# Pinout_Toygether_Sch.net
KiCad netlist of a schematic drawn in Altium Designer
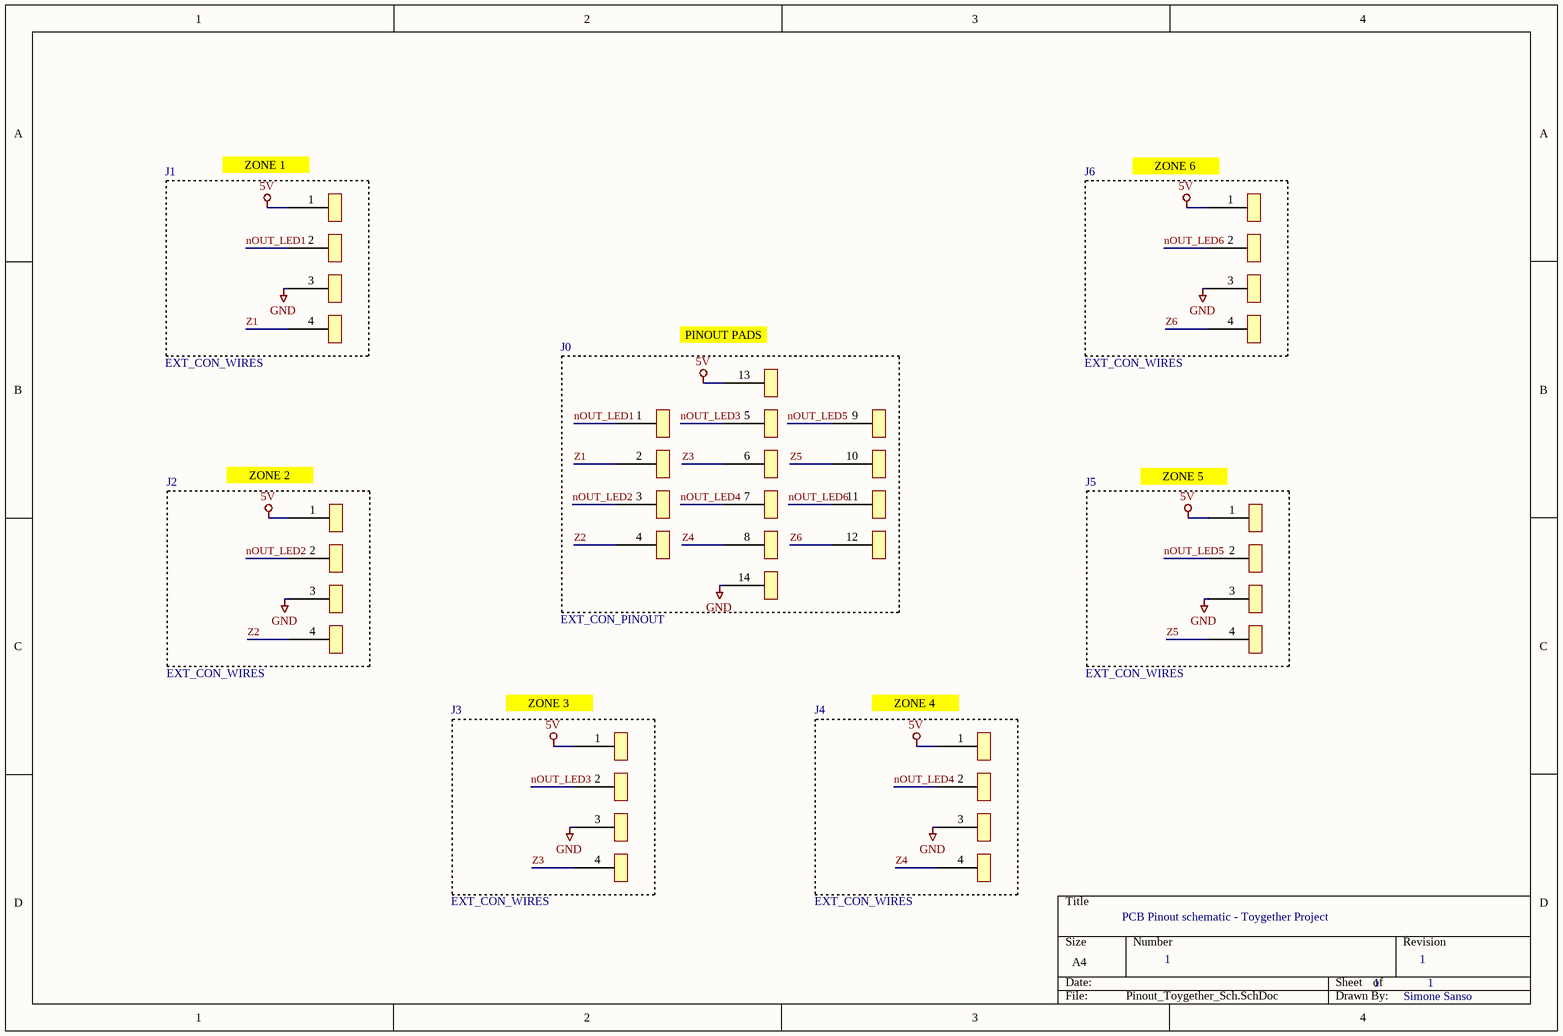
[diagram p0: Pinout_Toygether_Sch.SchDoc]

(export (version "E")
  (design (tool "Eeschema 10.0.6"))
  (components
    (comp (ref "J0")
      (value "EXT_CON_PINOUT")
      (footprint "EXT_CON_PINOUT_14P")
      (description "Pinout for the LEDs and capacitive touch sensors (on the plush toy)")
      (libsource (lib "Toygether_Schlib") (part "EXT_CON_PINOUT"))
    )
    (comp (ref "J1")
      (value "EXT_CON_WIRES")
      (footprint "EXT_CON_WIRES_4P")
      (description "Pads between pinout board and wires of the plush toy")
      (libsource (lib "Toygether_Schlib") (part "EXT_CON_WIRES"))
    )
    (comp (ref "J2")
      (value "EXT_CON_WIRES")
      (footprint "EXT_CON_WIRES_4P")
      (description "Pads between pinout board and wires of the plush toy")
      (libsource (lib "Toygether_Schlib") (part "EXT_CON_WIRES"))
    )
    (comp (ref "J3")
      (value "EXT_CON_WIRES")
      (footprint "EXT_CON_WIRES_4P")
      (description "Pads between pinout board and wires of the plush toy")
      (libsource (lib "Toygether_Schlib") (part "EXT_CON_WIRES"))
    )
    (comp (ref "J4")
      (value "EXT_CON_WIRES")
      (footprint "EXT_CON_WIRES_4P")
      (description "Pads between pinout board and wires of the plush toy")
      (libsource (lib "Toygether_Schlib") (part "EXT_CON_WIRES"))
    )
    (comp (ref "J5")
      (value "EXT_CON_WIRES")
      (footprint "EXT_CON_WIRES_4P")
      (description "Pads between pinout board and wires of the plush toy")
      (libsource (lib "Toygether_Schlib") (part "EXT_CON_WIRES"))
    )
    (comp (ref "J6")
      (value "EXT_CON_WIRES")
      (footprint "EXT_CON_WIRES_4P")
      (description "Pads between pinout board and wires of the plush toy")
      (libsource (lib "Toygether_Schlib") (part "EXT_CON_WIRES"))
    )
  )
  (nets
    (net (code "1") (name "/Z1") (class "Default")
      (node (ref "J0") (pin "2") (pintype "passive"))
      (node (ref "J1") (pin "4") (pintype "passive"))
    )
    (net (code "2") (name "/Z2") (class "Default")
      (node (ref "J0") (pin "4") (pintype "passive"))
      (node (ref "J2") (pin "4") (pintype "passive"))
    )
    (net (code "3") (name "/Z3") (class "Default")
      (node (ref "J0") (pin "6") (pintype "passive"))
      (node (ref "J3") (pin "4") (pintype "passive"))
    )
    (net (code "4") (name "/Z4") (class "Default")
      (node (ref "J0") (pin "8") (pintype "passive"))
      (node (ref "J4") (pin "4") (pintype "passive"))
    )
    (net (code "5") (name "/Z5") (class "Default")
      (node (ref "J0") (pin "10") (pintype "passive"))
      (node (ref "J5") (pin "4") (pintype "passive"))
    )
    (net (code "6") (name "/Z6") (class "Default")
      (node (ref "J0") (pin "12") (pintype "passive"))
      (node (ref "J6") (pin "4") (pintype "passive"))
    )
    (net (code "7") (name "/nOUT_LED1") (class "Default")
      (node (ref "J0") (pin "1") (pintype "passive"))
      (node (ref "J1") (pin "2") (pintype "passive"))
    )
    (net (code "8") (name "/nOUT_LED2") (class "Default")
      (node (ref "J0") (pin "3") (pintype "passive"))
      (node (ref "J2") (pin "2") (pintype "passive"))
    )
    (net (code "9") (name "/nOUT_LED3") (class "Default")
      (node (ref "J0") (pin "5") (pintype "passive"))
      (node (ref "J3") (pin "2") (pintype "passive"))
    )
    (net (code "10") (name "/nOUT_LED4") (class "Default")
      (node (ref "J0") (pin "7") (pintype "passive"))
      (node (ref "J4") (pin "2") (pintype "passive"))
    )
    (net (code "11") (name "/nOUT_LED5") (class "Default")
      (node (ref "J0") (pin "9") (pintype "passive"))
      (node (ref "J5") (pin "2") (pintype "passive"))
    )
    (net (code "12") (name "/nOUT_LED6") (class "Default")
      (node (ref "J0") (pin "11") (pintype "passive"))
      (node (ref "J6") (pin "2") (pintype "passive"))
    )
    (net (code "13") (name "5V") (class "Default")
      (node (ref "J0") (pin "13") (pintype "passive"))
      (node (ref "J1") (pin "1") (pintype "passive"))
      (node (ref "J2") (pin "1") (pintype "passive"))
      (node (ref "J3") (pin "1") (pintype "passive"))
      (node (ref "J4") (pin "1") (pintype "passive"))
      (node (ref "J5") (pin "1") (pintype "passive"))
      (node (ref "J6") (pin "1") (pintype "passive"))
    )
    (net (code "14") (name "GND") (class "Default")
      (node (ref "J0") (pin "14") (pintype "passive"))
      (node (ref "J1") (pin "3") (pintype "passive"))
      (node (ref "J2") (pin "3") (pintype "passive"))
      (node (ref "J3") (pin "3") (pintype "passive"))
      (node (ref "J4") (pin "3") (pintype "passive"))
      (node (ref "J5") (pin "3") (pintype "passive"))
      (node (ref "J6") (pin "3") (pintype "passive"))
    )
  )
)
